# ProtoStack_Codec.net
KiCad netlist of a schematic drawn in Altium Designer
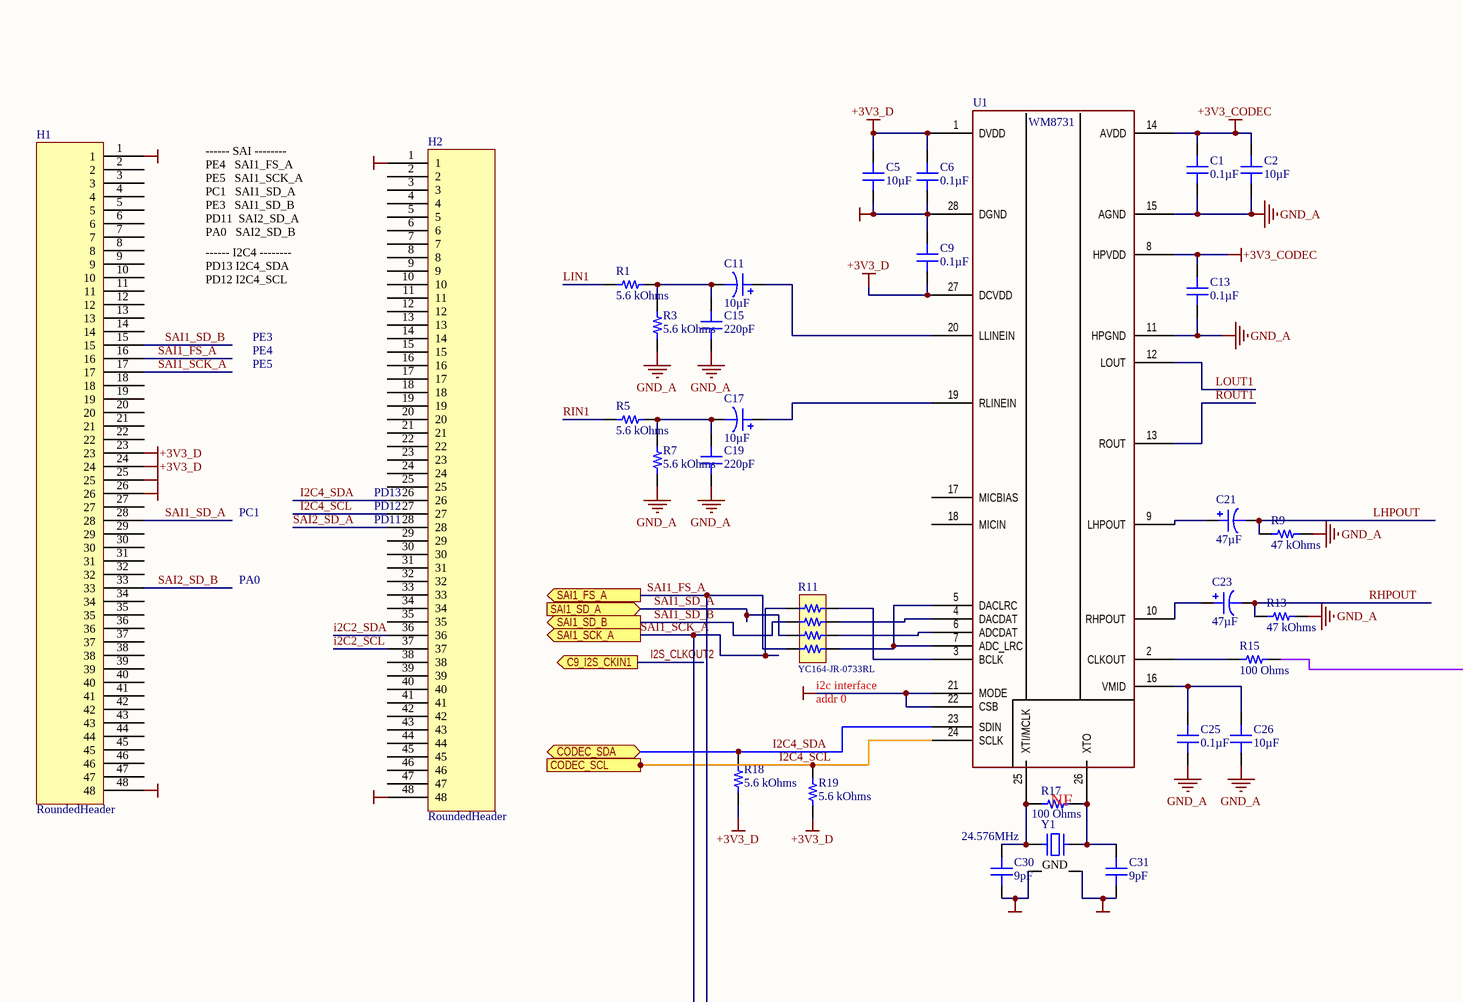
[diagram p0: ProtoStack_Codec.SchDoc, left]
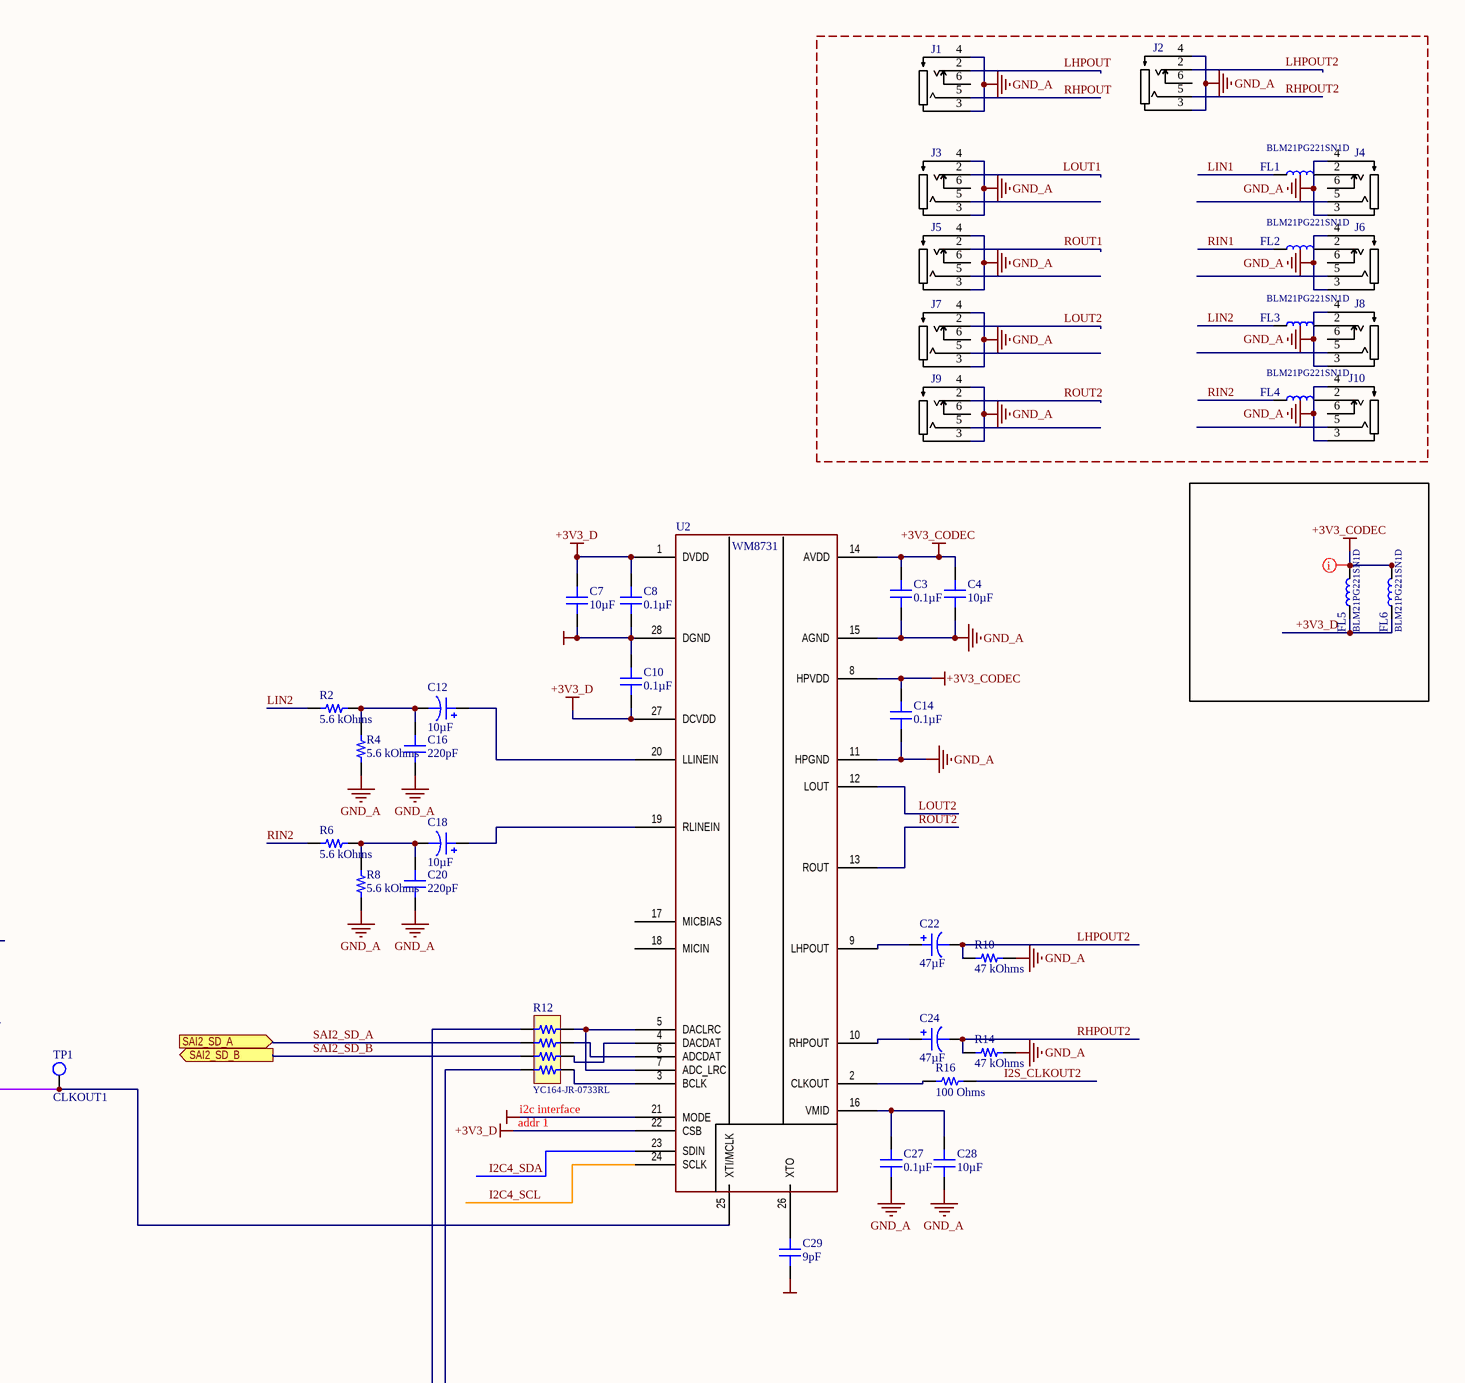
[diagram p1: ProtoStack_Codec.SchDoc, right]

(export (version "E")
  (design (tool "Eeschema 10.0.6"))
  (components
    (comp (ref "C1")
      (value "0.1µF")
      (footprint "CAP 0402_1005")
      (description "CAP CER 0.1UF 16V X7R 0402")
      (fields (field (name "PART NUMBER") "C0402C104K4RACAUTO") (field (name "MANUFACTURER") "KEMET"))
      (libsource (lib "Celestial Altium Library - altium_library") (part "Capacitor"))
    )
    (comp (ref "C2")
      (value "10µF")
      (footprint "CAP 0805_2012")
      (description "CAP CER 10UF 10V X5R 0805")
      (fields (field (name "PART NUMBER") "C0805C106K8PACTU") (field (name "MANUFACTURER") "KEMET"))
      (libsource (lib "Celestial Altium Library - altium_library") (part "Capacitor"))
    )
    (comp (ref "C3")
      (value "0.1µF")
      (footprint "CAP 0402_1005")
      (description "CAP CER 0.1UF 16V X7R 0402")
      (fields (field (name "PART NUMBER") "C0402C104K4RACAUTO") (field (name "MANUFACTURER") "KEMET"))
      (libsource (lib "Celestial Altium Library - altium_library") (part "Capacitor"))
    )
    (comp (ref "C4")
      (value "10µF")
      (footprint "CAP 0805_2012")
      (description "CAP CER 10UF 10V X5R 0805")
      (fields (field (name "PART NUMBER") "C0805C106K8PACTU") (field (name "MANUFACTURER") "KEMET"))
      (libsource (lib "Celestial Altium Library - altium_library") (part "Capacitor"))
    )
    (comp (ref "C5")
      (value "10µF")
      (footprint "CAP 0805_2012")
      (description "CAP CER 10UF 10V X5R 0805")
      (fields (field (name "PART NUMBER") "C0805C106K8PACTU") (field (name "MANUFACTURER") "KEMET"))
      (libsource (lib "Celestial Altium Library - altium_library") (part "Capacitor"))
    )
    (comp (ref "C6")
      (value "0.1µF")
      (footprint "CAP 0402_1005")
      (description "CAP CER 0.1UF 16V X7R 0402")
      (fields (field (name "PART NUMBER") "C0402C104K4RACAUTO") (field (name "MANUFACTURER") "KEMET"))
      (libsource (lib "Celestial Altium Library - altium_library") (part "Capacitor"))
    )
    (comp (ref "C7")
      (value "10µF")
      (footprint "CAP 0805_2012")
      (description "CAP CER 10UF 10V X5R 0805")
      (fields (field (name "PART NUMBER") "C0805C106K8PACTU") (field (name "MANUFACTURER") "KEMET"))
      (libsource (lib "Celestial Altium Library - altium_library") (part "Capacitor"))
    )
    (comp (ref "C8")
      (value "0.1µF")
      (footprint "CAP 0402_1005")
      (description "CAP CER 0.1UF 16V X7R 0402")
      (fields (field (name "PART NUMBER") "C0402C104K4RACAUTO") (field (name "MANUFACTURER") "KEMET"))
      (libsource (lib "Celestial Altium Library - altium_library") (part "Capacitor"))
    )
    (comp (ref "C9")
      (value "0.1µF")
      (footprint "CAP 0402_1005")
      (description "CAP CER 0.1UF 16V X7R 0402")
      (fields (field (name "PART NUMBER") "C0402C104K4RACAUTO") (field (name "MANUFACTURER") "KEMET"))
      (libsource (lib "Celestial Altium Library - altium_library") (part "Capacitor"))
    )
    (comp (ref "C10")
      (value "0.1µF")
      (footprint "CAP 0402_1005")
      (description "CAP CER 0.1UF 16V X7R 0402")
      (fields (field (name "PART NUMBER") "C0402C104K4RACAUTO") (field (name "MANUFACTURER") "KEMET"))
      (libsource (lib "Celestial Altium Library - altium_library") (part "Capacitor"))
    )
    (comp (ref "C11")
      (value "10µF")
      (footprint "CAP POL 1206_3216")
      (description "CAP TANT 10UF 10% 10V 1206")
      (fields (field (name "PART NUMBER") "T491A106K010AT") (field (name "MANUFACTURER") "KEMET"))
      (libsource (lib "Celestial Altium Library - altium_library") (part "Polarised Capacitor"))
    )
    (comp (ref "C12")
      (value "10µF")
      (footprint "CAP POL 1206_3216")
      (description "CAP TANT 10UF 10% 10V 1206")
      (fields (field (name "PART NUMBER") "T491A106K010AT") (field (name "MANUFACTURER") "KEMET"))
      (libsource (lib "Celestial Altium Library - altium_library") (part "Polarised Capacitor"))
    )
    (comp (ref "C13")
      (value "0.1µF")
      (footprint "CAP 0402_1005")
      (description "CAP CER 0.1UF 16V X7R 0402")
      (fields (field (name "PART NUMBER") "C0402C104K4RACAUTO") (field (name "MANUFACTURER") "KEMET"))
      (libsource (lib "Celestial Altium Library - altium_library") (part "Capacitor"))
    )
    (comp (ref "C14")
      (value "0.1µF")
      (footprint "CAP 0402_1005")
      (description "CAP CER 0.1UF 16V X7R 0402")
      (fields (field (name "PART NUMBER") "C0402C104K4RACAUTO") (field (name "MANUFACTURER") "KEMET"))
      (libsource (lib "Celestial Altium Library - altium_library") (part "Capacitor"))
    )
    (comp (ref "C15")
      (value "220pF")
      (footprint "CAP 0603_1608")
      (description "CAP CER 220PF 50V X7R 0603")
      (fields (field (name "PART NUMBER") "C0603C221K5RACTU") (field (name "MANUFACTURER") "KEMET"))
      (libsource (lib "Celestial Altium Library - altium_library") (part "Capacitor"))
    )
    (comp (ref "C16")
      (value "220pF")
      (footprint "CAP 0603_1608")
      (description "CAP CER 220PF 50V X7R 0603")
      (fields (field (name "PART NUMBER") "C0603C221K5RACTU") (field (name "MANUFACTURER") "KEMET"))
      (libsource (lib "Celestial Altium Library - altium_library") (part "Capacitor"))
    )
    (comp (ref "C17")
      (value "10µF")
      (footprint "CAP POL 1206_3216")
      (description "CAP TANT 10UF 10% 10V 1206")
      (fields (field (name "PART NUMBER") "T491A106K010AT") (field (name "MANUFACTURER") "KEMET"))
      (libsource (lib "Celestial Altium Library - altium_library") (part "Polarised Capacitor"))
    )
    (comp (ref "C18")
      (value "10µF")
      (footprint "CAP POL 1206_3216")
      (description "CAP TANT 10UF 10% 10V 1206")
      (fields (field (name "PART NUMBER") "T491A106K010AT") (field (name "MANUFACTURER") "KEMET"))
      (libsource (lib "Celestial Altium Library - altium_library") (part "Polarised Capacitor"))
    )
    (comp (ref "C19")
      (value "220pF")
      (footprint "CAP 0603_1608")
      (description "CAP CER 220PF 50V X7R 0603")
      (fields (field (name "PART NUMBER") "C0603C221K5RACTU") (field (name "MANUFACTURER") "KEMET"))
      (libsource (lib "Celestial Altium Library - altium_library") (part "Capacitor"))
    )
    (comp (ref "C20")
      (value "220pF")
      (footprint "CAP 0603_1608")
      (description "CAP CER 220PF 50V X7R 0603")
      (fields (field (name "PART NUMBER") "C0603C221K5RACTU") (field (name "MANUFACTURER") "KEMET"))
      (libsource (lib "Celestial Altium Library - altium_library") (part "Capacitor"))
    )
    (comp (ref "C21")
      (value "47µF")
      (footprint "CAP POL 2917_7343")
      (description "CAP TANT 47UF 10% 10V 2917")
      (fields (field (name "PART NUMBER") "293D476X9010D2TE3") (field (name "MANUFACTURER") "Vishay Sprague"))
      (libsource (lib "Celestial Altium Library - altium_library") (part "Polarised Capacitor"))
    )
    (comp (ref "C22")
      (value "47µF")
      (footprint "CAP POL 2917_7343")
      (description "CAP TANT 47UF 10% 10V 2917")
      (fields (field (name "PART NUMBER") "293D476X9010D2TE3") (field (name "MANUFACTURER") "Vishay Sprague"))
      (libsource (lib "Celestial Altium Library - altium_library") (part "Polarised Capacitor"))
    )
    (comp (ref "C23")
      (value "47µF")
      (footprint "CAP POL 2917_7343")
      (description "CAP TANT 47UF 10% 10V 2917")
      (fields (field (name "PART NUMBER") "293D476X9010D2TE3") (field (name "MANUFACTURER") "Vishay Sprague"))
      (libsource (lib "Celestial Altium Library - altium_library") (part "Polarised Capacitor"))
    )
    (comp (ref "C24")
      (value "47µF")
      (footprint "CAP POL 2917_7343")
      (description "CAP TANT 47UF 10% 10V 2917")
      (fields (field (name "PART NUMBER") "293D476X9010D2TE3") (field (name "MANUFACTURER") "Vishay Sprague"))
      (libsource (lib "Celestial Altium Library - altium_library") (part "Polarised Capacitor"))
    )
    (comp (ref "C25")
      (value "0.1µF")
      (footprint "CAP 0402_1005")
      (description "CAP CER 0.1UF 16V X7R 0402")
      (fields (field (name "PART NUMBER") "C0402C104K4RACAUTO") (field (name "MANUFACTURER") "KEMET"))
      (libsource (lib "Celestial Altium Library - altium_library") (part "Capacitor"))
    )
    (comp (ref "C26")
      (value "10µF")
      (footprint "CAP 0805_2012")
      (description "CAP CER 10UF 10V X5R 0805")
      (fields (field (name "PART NUMBER") "C0805C106K8PACTU") (field (name "MANUFACTURER") "KEMET"))
      (libsource (lib "Celestial Altium Library - altium_library") (part "Capacitor"))
    )
    (comp (ref "C27")
      (value "0.1µF")
      (footprint "CAP 0402_1005")
      (description "CAP CER 0.1UF 16V X7R 0402")
      (fields (field (name "PART NUMBER") "C0402C104K4RACAUTO") (field (name "MANUFACTURER") "KEMET"))
      (libsource (lib "Celestial Altium Library - altium_library") (part "Capacitor"))
    )
    (comp (ref "C28")
      (value "10µF")
      (footprint "CAP 0805_2012")
      (description "CAP CER 10UF 10V X5R 0805")
      (fields (field (name "PART NUMBER") "C0805C106K8PACTU") (field (name "MANUFACTURER") "KEMET"))
      (libsource (lib "Celestial Altium Library - altium_library") (part "Capacitor"))
    )
    (comp (ref "C29")
      (value "9pF")
      (footprint "CAP 0805_2012")
      (description "CAP CER 9PF 250V C0G/NP0 0805")
      (fields (field (name "PART NUMBER") "CBR08C909CAGAC") (field (name "MANUFACTURER") "KEMET"))
      (libsource (lib "Celestial Altium Library - altium_library") (part "Capacitor"))
    )
    (comp (ref "C30")
      (value "9pF")
      (footprint "CAP 0805_2012")
      (description "CAP CER 9PF 250V C0G/NP0 0805")
      (fields (field (name "PART NUMBER") "CBR08C909CAGAC") (field (name "MANUFACTURER") "KEMET"))
      (libsource (lib "Celestial Altium Library - altium_library") (part "Capacitor"))
    )
    (comp (ref "C31")
      (value "9pF")
      (footprint "CAP 0805_2012")
      (description "CAP CER 9PF 250V C0G/NP0 0805")
      (fields (field (name "PART NUMBER") "CBR08C909CAGAC") (field (name "MANUFACTURER") "KEMET"))
      (libsource (lib "Celestial Altium Library - altium_library") (part "Capacitor"))
    )
    (comp (ref "FL1")
      (value "BLM21PG221SN1D")
      (footprint "0805_IND")
      (description "ACM Series 0805 360 Ohm 220mA 500 mOhm DCR 50 V SMT Common Mode Filter")
      (libsource (lib "ProtoStack_H750VBT") (part "BLM21PG221SN1D"))
    )
    (comp (ref "FL2")
      (value "BLM21PG221SN1D")
      (footprint "0805_IND")
      (description "ACM Series 0805 360 Ohm 220mA 500 mOhm DCR 50 V SMT Common Mode Filter")
      (libsource (lib "ProtoStack_H750VBT") (part "BLM21PG221SN1D"))
    )
    (comp (ref "FL3")
      (value "BLM21PG221SN1D")
      (footprint "0805_IND")
      (description "ACM Series 0805 360 Ohm 220mA 500 mOhm DCR 50 V SMT Common Mode Filter")
      (libsource (lib "ProtoStack_H750VBT") (part "BLM21PG221SN1D"))
    )
    (comp (ref "FL4")
      (value "BLM21PG221SN1D")
      (footprint "0805_IND")
      (description "ACM Series 0805 360 Ohm 220mA 500 mOhm DCR 50 V SMT Common Mode Filter")
      (libsource (lib "ProtoStack_H750VBT") (part "BLM21PG221SN1D"))
    )
    (comp (ref "FL5")
      (value "BLM21PG221SN1D")
      (footprint "0805_IND")
      (description "ACM Series 0805 360 Ohm 220mA 500 mOhm DCR 50 V SMT Common Mode Filter")
      (libsource (lib "") (part "BLM21PG221SN1D_1"))
    )
    (comp (ref "FL6")
      (value "BLM21PG221SN1D")
      (footprint "0805_IND")
      (description "ACM Series 0805 360 Ohm 220mA 500 mOhm DCR 50 V SMT Common Mode Filter")
      (libsource (lib "") (part "BLM21PG221SN1D_1"))
    )
    (comp (ref "H1")
      (value "RoundedHeader")
      (footprint "ProtoStack_H750VBT:HeaderDtack_48")
      (libsource (lib "") (part "HeaderStack_48_1"))
    )
    (comp (ref "H2")
      (value "RoundedHeader")
      (footprint "ProtoStack_H750VBT:HeaderDtack_48")
      (libsource (lib "ProtoStack_H750VBT") (part "HeaderStack_48"))
    )
    (comp (ref "J1")
      (value "~")
      (footprint "PJ_327")
      (description "Conn 3.5MM Stereo Jack F 3 POS Solder RA SMD 3 Terminal 1 Port T/R")
      (fields (field (name "MP") "35RASMT2BHNTRX") (field (name "MF") "Switchcraft"))
      (libsource (lib "ProtoStack_H750VBT") (part "3.5mm jack stereo smd"))
    )
    (comp (ref "J2")
      (value "~")
      (footprint "PJ_327")
      (description "Conn 3.5MM Stereo Jack F 3 POS Solder RA SMD 3 Terminal 1 Port T/R")
      (fields (field (name "MP") "35RASMT2BHNTRX") (field (name "MF") "Switchcraft"))
      (libsource (lib "ProtoStack_H750VBT") (part "3.5mm jack stereo smd"))
    )
    (comp (ref "J3")
      (value "~")
      (footprint "PJ_327")
      (description "Conn 3.5MM Stereo Jack F 3 POS Solder RA SMD 3 Terminal 1 Port T/R")
      (fields (field (name "MP") "35RASMT2BHNTRX") (field (name "MF") "Switchcraft"))
      (libsource (lib "ProtoStack_H750VBT") (part "3.5mm jack stereo smd"))
    )
    (comp (ref "J4")
      (value "~")
      (footprint "PJ_327")
      (description "Conn 3.5MM Stereo Jack F 3 POS Solder RA SMD 3 Terminal 1 Port T/R")
      (fields (field (name "MP") "35RASMT2BHNTRX") (field (name "MF") "Switchcraft"))
      (libsource (lib "ProtoStack_H750VBT") (part "3.5mm jack stereo smd"))
    )
    (comp (ref "J5")
      (value "~")
      (footprint "PJ_327")
      (description "Conn 3.5MM Stereo Jack F 3 POS Solder RA SMD 3 Terminal 1 Port T/R")
      (fields (field (name "MP") "35RASMT2BHNTRX") (field (name "MF") "Switchcraft"))
      (libsource (lib "ProtoStack_H750VBT") (part "3.5mm jack stereo smd"))
    )
    (comp (ref "J6")
      (value "~")
      (footprint "PJ_327")
      (description "Conn 3.5MM Stereo Jack F 3 POS Solder RA SMD 3 Terminal 1 Port T/R")
      (fields (field (name "MP") "35RASMT2BHNTRX") (field (name "MF") "Switchcraft"))
      (libsource (lib "ProtoStack_H750VBT") (part "3.5mm jack stereo smd"))
    )
    (comp (ref "J7")
      (value "~")
      (footprint "PJ_327")
      (description "Conn 3.5MM Stereo Jack F 3 POS Solder RA SMD 3 Terminal 1 Port T/R")
      (fields (field (name "MP") "35RASMT2BHNTRX") (field (name "MF") "Switchcraft"))
      (libsource (lib "ProtoStack_H750VBT") (part "3.5mm jack stereo smd"))
    )
    (comp (ref "J8")
      (value "~")
      (footprint "PJ_327")
      (description "Conn 3.5MM Stereo Jack F 3 POS Solder RA SMD 3 Terminal 1 Port T/R")
      (fields (field (name "MP") "35RASMT2BHNTRX") (field (name "MF") "Switchcraft"))
      (libsource (lib "ProtoStack_H750VBT") (part "3.5mm jack stereo smd"))
    )
    (comp (ref "J9")
      (value "~")
      (footprint "PJ_327")
      (description "Conn 3.5MM Stereo Jack F 3 POS Solder RA SMD 3 Terminal 1 Port T/R")
      (fields (field (name "MP") "35RASMT2BHNTRX") (field (name "MF") "Switchcraft"))
      (libsource (lib "ProtoStack_H750VBT") (part "3.5mm jack stereo smd"))
    )
    (comp (ref "J10")
      (value "~")
      (footprint "PJ_327")
      (description "Conn 3.5MM Stereo Jack F 3 POS Solder RA SMD 3 Terminal 1 Port T/R")
      (fields (field (name "MP") "35RASMT2BHNTRX") (field (name "MF") "Switchcraft"))
      (libsource (lib "ProtoStack_H750VBT") (part "3.5mm jack stereo smd"))
    )
    (comp (ref "R1")
      (value "5.6 kOhms")
      (footprint "RES 0603_1608")
      (description "RES SMD 5.6K OHM 0.5% 1/10W 0603")
      (fields (field (name "PART NUMBER") "RT0603DRE075K6L") (field (name "MANUFACTURER") "Yageo"))
      (libsource (lib "Celestial Altium Library - altium_library") (part "Resistor"))
    )
    (comp (ref "R2")
      (value "5.6 kOhms")
      (footprint "RES 0603_1608")
      (description "RES SMD 5.6K OHM 0.5% 1/10W 0603")
      (fields (field (name "PART NUMBER") "RT0603DRE075K6L") (field (name "MANUFACTURER") "Yageo"))
      (libsource (lib "Celestial Altium Library - altium_library") (part "Resistor"))
    )
    (comp (ref "R3")
      (value "5.6 kOhms")
      (footprint "RES 0603_1608")
      (description "RES SMD 5.6K OHM 0.5% 1/10W 0603")
      (fields (field (name "PART NUMBER") "RT0603DRE075K6L") (field (name "MANUFACTURER") "Yageo"))
      (libsource (lib "Celestial Altium Library - altium_library") (part "Resistor"))
    )
    (comp (ref "R4")
      (value "5.6 kOhms")
      (footprint "RES 0603_1608")
      (description "RES SMD 5.6K OHM 0.5% 1/10W 0603")
      (fields (field (name "PART NUMBER") "RT0603DRE075K6L") (field (name "MANUFACTURER") "Yageo"))
      (libsource (lib "Celestial Altium Library - altium_library") (part "Resistor"))
    )
    (comp (ref "R5")
      (value "5.6 kOhms")
      (footprint "RES 0603_1608")
      (description "RES SMD 5.6K OHM 0.5% 1/10W 0603")
      (fields (field (name "PART NUMBER") "RT0603DRE075K6L") (field (name "MANUFACTURER") "Yageo"))
      (libsource (lib "Celestial Altium Library - altium_library") (part "Resistor"))
    )
    (comp (ref "R6")
      (value "5.6 kOhms")
      (footprint "RES 0603_1608")
      (description "RES SMD 5.6K OHM 0.5% 1/10W 0603")
      (fields (field (name "PART NUMBER") "RT0603DRE075K6L") (field (name "MANUFACTURER") "Yageo"))
      (libsource (lib "Celestial Altium Library - altium_library") (part "Resistor"))
    )
    (comp (ref "R7")
      (value "5.6 kOhms")
      (footprint "RES 0603_1608")
      (description "RES SMD 5.6K OHM 0.5% 1/10W 0603")
      (fields (field (name "PART NUMBER") "RT0603DRE075K6L") (field (name "MANUFACTURER") "Yageo"))
      (libsource (lib "Celestial Altium Library - altium_library") (part "Resistor"))
    )
    (comp (ref "R8")
      (value "5.6 kOhms")
      (footprint "RES 0603_1608")
      (description "RES SMD 5.6K OHM 0.5% 1/10W 0603")
      (fields (field (name "PART NUMBER") "RT0603DRE075K6L") (field (name "MANUFACTURER") "Yageo"))
      (libsource (lib "Celestial Altium Library - altium_library") (part "Resistor"))
    )
    (comp (ref "R9")
      (value "47 kOhms")
      (footprint "RES 0603_1608")
      (description "RES SMD 47K OHM 1% 1/10W 0603")
      (fields (field (name "PART NUMBER") "RT0603FRE0747KL") (field (name "MANUFACTURER") "Yageo"))
      (libsource (lib "Celestial Altium Library - altium_library") (part "Resistor"))
    )
    (comp (ref "R10")
      (value "47 kOhms")
      (footprint "RES 0603_1608")
      (description "RES SMD 47K OHM 1% 1/10W 0603")
      (fields (field (name "PART NUMBER") "RT0603FRE0747KL") (field (name "MANUFACTURER") "Yageo"))
      (libsource (lib "Celestial Altium Library - altium_library") (part "Resistor"))
    )
    (comp (ref "R11")
      (value "YC164-JR-0733RL")
      (footprint "RESNET 1206-8 CONVEX")
      (description "RES ARRAY 4 RES 33 OHM 1206")
      (fields (field (name "MANUFACTURER") "Yageo") (field (name "TOLERANCE") "±5%"))
      (libsource (lib "Celestial Altium Library - altium_library") (part "Resistor Array (4 circuit)"))
    )
    (comp (ref "R12")
      (value "YC164-JR-0733RL")
      (footprint "RESNET 1206-8 CONVEX")
      (description "RES ARRAY 4 RES 33 OHM 1206")
      (fields (field (name "MANUFACTURER") "Yageo") (field (name "TOLERANCE") "±5%"))
      (libsource (lib "Celestial Altium Library - altium_library") (part "Resistor Array (4 circuit)"))
    )
    (comp (ref "R13")
      (value "47 kOhms")
      (footprint "RES 0603_1608")
      (description "RES SMD 47K OHM 1% 1/10W 0603")
      (fields (field (name "PART NUMBER") "RT0603FRE0747KL") (field (name "MANUFACTURER") "Yageo"))
      (libsource (lib "Celestial Altium Library - altium_library") (part "Resistor"))
    )
    (comp (ref "R14")
      (value "47 kOhms")
      (footprint "RES 0603_1608")
      (description "RES SMD 47K OHM 1% 1/10W 0603")
      (fields (field (name "PART NUMBER") "RT0603FRE0747KL") (field (name "MANUFACTURER") "Yageo"))
      (libsource (lib "Celestial Altium Library - altium_library") (part "Resistor"))
    )
    (comp (ref "R15")
      (value "100 Ohms")
      (footprint "RES 0402_1005")
      (description "RES SMD 100 OHM 1% 1/16W 0402")
      (fields (field (name "PART NUMBER") "RT0402FRE07100RL") (field (name "MANUFACTURER") "Yageo"))
      (libsource (lib "Celestial Altium Library - altium_library") (part "Resistor"))
    )
    (comp (ref "R16")
      (value "100 Ohms")
      (footprint "RES 0402_1005")
      (description "RES SMD 100 OHM 1% 1/16W 0402")
      (fields (field (name "PART NUMBER") "RT0402FRE07100RL") (field (name "MANUFACTURER") "Yageo"))
      (libsource (lib "Celestial Altium Library - altium_library") (part "Resistor"))
    )
    (comp (ref "R17")
      (value "100 Ohms")
      (footprint "RES 0402_1005")
      (description "RES SMD 100 OHM 1% 1/16W 0402")
      (fields (field (name "PART NUMBER") "RT0402FRE07100RL") (field (name "MANUFACTURER") "Yageo"))
      (libsource (lib "Celestial Altium Library - altium_library") (part "Resistor"))
    )
    (comp (ref "R18")
      (value "5.6 kOhms")
      (footprint "RES 0603_1608")
      (description "RES SMD 5.6K OHM 0.5% 1/10W 0603")
      (fields (field (name "PART NUMBER") "RT0603DRE075K6L") (field (name "MANUFACTURER") "Yageo"))
      (libsource (lib "Celestial Altium Library - altium_library") (part "Resistor"))
    )
    (comp (ref "R19")
      (value "5.6 kOhms")
      (footprint "RES 0603_1608")
      (description "RES SMD 5.6K OHM 0.5% 1/10W 0603")
      (fields (field (name "PART NUMBER") "RT0603DRE075K6L") (field (name "MANUFACTURER") "Yageo"))
      (libsource (lib "Celestial Altium Library - altium_library") (part "Resistor"))
    )
    (comp (ref "TP1")
      (value "CLKOUT1")
      (footprint "TESTPOINT")
      (libsource (lib "DAC_ADC") (part "TestPoint"))
    )
    (comp (ref "U1")
      (value "WM8731")
      (footprint "TSSOP-28")
      (description "Stero in/ot audio codec")
      (libsource (lib "DAC_ADC") (part "WM8731"))
    )
    (comp (ref "U2")
      (value "WM8731")
      (footprint "TSSOP-28")
      (description "Stero in/ot audio codec")
      (libsource (lib "DAC_ADC") (part "WM8731"))
    )
    (comp (ref "Y1")
      (value "24.576MHz")
      (footprint "ABRACON ABM8G")
      (description "CRYSTAL 24.5760MHZ 10PF SMD")
      (fields
        (field (name "PART NUMBER") "ABM8G-24.576MHZ-B4Y-T")
        (field (name "MANUFACTURER") "Abracon LLC")
      )
      (libsource (lib "Celestial Altium Library - altium_library") (part "Abracon Crystal ABM8G"))
    )
  )
  (nets
    (net (code "1") (name "+3V3_CODEC") (class "Default")
      (node (ref "C1") (pin "2") (pinfunction "2_2") (pintype "passive"))
      (node (ref "C13") (pin "2") (pinfunction "2_2") (pintype "passive"))
      (node (ref "C14") (pin "2") (pinfunction "2_2") (pintype "passive"))
      (node (ref "C2") (pin "2") (pinfunction "2_2") (pintype "passive"))
      (node (ref "C3") (pin "2") (pinfunction "2_2") (pintype "passive"))
      (node (ref "C4") (pin "2") (pinfunction "2_2") (pintype "passive"))
      (node (ref "FL5") (pin "2") (pinfunction "2_2") (pintype "passive"))
      (node (ref "FL6") (pin "2") (pinfunction "2_2") (pintype "passive"))
      (node (ref "U1") (pin "14") (pinfunction "AVDD_14") (pintype "passive"))
      (node (ref "U1") (pin "8") (pinfunction "HPVDD_8") (pintype "passive"))
      (node (ref "U2") (pin "14") (pinfunction "AVDD_14") (pintype "passive"))
      (node (ref "U2") (pin "8") (pinfunction "HPVDD_8") (pintype "passive"))
    )
    (net (code "2") (name "+3V3_D") (class "Default")
      (node (ref "C10") (pin "1") (pinfunction "1_1") (pintype "passive"))
      (node (ref "C5") (pin "2") (pinfunction "2_2") (pintype "passive"))
      (node (ref "C6") (pin "2") (pinfunction "2_2") (pintype "passive"))
      (node (ref "C7") (pin "2") (pinfunction "2_2") (pintype "passive"))
      (node (ref "C8") (pin "2") (pinfunction "2_2") (pintype "passive"))
      (node (ref "C9") (pin "1") (pinfunction "1_1") (pintype "passive"))
      (node (ref "FL5") (pin "1") (pinfunction "1_1") (pintype "passive"))
      (node (ref "FL6") (pin "1") (pinfunction "1_1") (pintype "passive"))
      (node (ref "H1") (pin "23") (pinfunction "23_23") (pintype "passive"))
      (node (ref "H1") (pin "24") (pinfunction "24_24") (pintype "passive"))
      (node (ref "R18") (pin "1") (pinfunction "1_1") (pintype "passive"))
      (node (ref "R19") (pin "1") (pinfunction "1_1") (pintype "passive"))
      (node (ref "U1") (pin "1") (pinfunction "DVDD_1") (pintype "passive"))
      (node (ref "U1") (pin "27") (pinfunction "DCVDD_27") (pintype "passive"))
      (node (ref "U2") (pin "1") (pinfunction "DVDD_1") (pintype "passive"))
      (node (ref "U2") (pin "22") (pinfunction "CSB_22") (pintype "passive"))
      (node (ref "U2") (pin "27") (pinfunction "DCVDD_27") (pintype "passive"))
    )
    (net (code "3") (name "/I2C4_SCL") (class "Default")
      (node (ref "H2") (pin "27") (pinfunction "27_27") (pintype "passive"))
      (node (ref "R19") (pin "2") (pinfunction "2_2") (pintype "passive"))
      (node (ref "U1") (pin "24") (pinfunction "SCLK_24") (pintype "passive"))
      (node (ref "U2") (pin "24") (pinfunction "SCLK_24") (pintype "passive"))
    )
    (net (code "4") (name "/I2C4_SDA") (class "Default")
      (node (ref "H2") (pin "26") (pinfunction "26_26") (pintype "passive"))
      (node (ref "R18") (pin "2") (pinfunction "2_2") (pintype "passive"))
      (node (ref "U1") (pin "23") (pinfunction "SDIN_23") (pintype "passive"))
      (node (ref "U2") (pin "23") (pinfunction "SDIN_23") (pintype "passive"))
    )
    (net (code "5") (name "/I2S_CLKOUT2") (class "Default")
      (node (ref "R16") (pin "2") (pinfunction "2_2") (pintype "passive"))
    )
    (net (code "6") (name "/LHPOUT") (class "Default")
      (node (ref "C21") (pin "2") (pinfunction "2_2") (pintype "passive"))
      (node (ref "J1") (pin "2") (pinfunction "2_2") (pintype "passive"))
      (node (ref "R9") (pin "1") (pinfunction "1_1") (pintype "passive"))
    )
    (net (code "7") (name "/LHPOUT2") (class "Default")
      (node (ref "C22") (pin "2") (pinfunction "2_2") (pintype "passive"))
      (node (ref "J2") (pin "2") (pinfunction "2_2") (pintype "passive"))
      (node (ref "R10") (pin "1") (pinfunction "1_1") (pintype "passive"))
    )
    (net (code "8") (name "/LIN1") (class "Default")
      (node (ref "FL1") (pin "1") (pinfunction "1_1") (pintype "passive"))
      (node (ref "R1") (pin "1") (pinfunction "1_1") (pintype "passive"))
    )
    (net (code "9") (name "/LIN2") (class "Default")
      (node (ref "FL3") (pin "1") (pinfunction "1_1") (pintype "passive"))
      (node (ref "R2") (pin "1") (pinfunction "1_1") (pintype "passive"))
    )
    (net (code "10") (name "/LOUT1") (class "Default")
      (node (ref "J3") (pin "2") (pinfunction "2_2") (pintype "passive"))
      (node (ref "U1") (pin "12") (pinfunction "LOUT_12") (pintype "passive"))
    )
    (net (code "11") (name "/LOUT2") (class "Default")
      (node (ref "J7") (pin "2") (pinfunction "2_2") (pintype "passive"))
      (node (ref "U2") (pin "12") (pinfunction "LOUT_12") (pintype "passive"))
    )
    (net (code "12") (name "/RHPOUT") (class "Default")
      (node (ref "C23") (pin "2") (pinfunction "2_2") (pintype "passive"))
      (node (ref "J1") (pin "5") (pinfunction "3_5") (pintype "passive"))
      (node (ref "R13") (pin "1") (pinfunction "1_1") (pintype "passive"))
    )
    (net (code "13") (name "/RHPOUT2") (class "Default")
      (node (ref "C24") (pin "2") (pinfunction "2_2") (pintype "passive"))
      (node (ref "J2") (pin "5") (pinfunction "3_5") (pintype "passive"))
      (node (ref "R14") (pin "1") (pinfunction "1_1") (pintype "passive"))
    )
    (net (code "14") (name "/RIN1") (class "Default")
      (node (ref "FL2") (pin "1") (pinfunction "1_1") (pintype "passive"))
      (node (ref "R5") (pin "1") (pinfunction "1_1") (pintype "passive"))
    )
    (net (code "15") (name "/RIN2") (class "Default")
      (node (ref "FL4") (pin "1") (pinfunction "1_1") (pintype "passive"))
      (node (ref "R6") (pin "1") (pinfunction "1_1") (pintype "passive"))
    )
    (net (code "16") (name "/ROUT1") (class "Default")
      (node (ref "J5") (pin "2") (pinfunction "2_2") (pintype "passive"))
      (node (ref "U1") (pin "13") (pinfunction "ROUT_13") (pintype "passive"))
    )
    (net (code "17") (name "/ROUT2") (class "Default")
      (node (ref "J9") (pin "2") (pinfunction "2_2") (pintype "passive"))
      (node (ref "U2") (pin "13") (pinfunction "ROUT_13") (pintype "passive"))
    )
    (net (code "18") (name "/SAI1_FS_A") (class "Default")
      (node (ref "H1") (pin "16") (pinfunction "16_16") (pintype "passive"))
      (node (ref "R11") (pin "4") (pinfunction "4_4") (pintype "passive"))
      (node (ref "R12") (pin "1") (pinfunction "1_1") (pintype "passive"))
    )
    (net (code "19") (name "/SAI1_SCK_A") (class "Default")
      (node (ref "H1") (pin "17") (pinfunction "17_17") (pintype "passive"))
      (node (ref "R11") (pin "1") (pinfunction "1_1") (pintype "passive"))
      (node (ref "R12") (pin "4") (pinfunction "4_4") (pintype "passive"))
    )
    (net (code "20") (name "/SAI1_SD_A") (class "Default")
      (node (ref "H1") (pin "28") (pinfunction "28_28") (pintype "passive"))
      (node (ref "R11") (pin "3") (pinfunction "3_3") (pintype "passive"))
    )
    (net (code "21") (name "/SAI1_SD_B") (class "Default")
      (node (ref "H1") (pin "15") (pinfunction "15_15") (pintype "passive"))
      (node (ref "R11") (pin "2") (pinfunction "2_2") (pintype "passive"))
    )
    (net (code "22") (name "/SAI2_SD_A") (class "Default")
      (node (ref "H2") (pin "28") (pinfunction "28_28") (pintype "passive"))
      (node (ref "R12") (pin "2") (pinfunction "2_2") (pintype "passive"))
    )
    (net (code "23") (name "/SAI2_SD_B") (class "Default")
      (node (ref "H1") (pin "33") (pinfunction "33_33") (pintype "passive"))
      (node (ref "R12") (pin "3") (pinfunction "3_3") (pintype "passive"))
    )
    (net (code "24") (name "/i2C2_SCL") (class "Default")
      (node (ref "H2") (pin "37") (pinfunction "37_37") (pintype "passive"))
    )
    (net (code "25") (name "/i2C2_SDA") (class "Default")
      (node (ref "H2") (pin "36") (pinfunction "36_36") (pintype "passive"))
    )
    (net (code "26") (name "GND") (class "Default")
      (node (ref "C10") (pin "2") (pinfunction "2_2") (pintype "passive"))
      (node (ref "C29") (pin "2") (pinfunction "2_2") (pintype "passive"))
      (node (ref "C30") (pin "2") (pinfunction "2_2") (pintype "passive"))
      (node (ref "C31") (pin "2") (pinfunction "2_2") (pintype "passive"))
      (node (ref "C5") (pin "1") (pinfunction "1_1") (pintype "passive"))
      (node (ref "C6") (pin "1") (pinfunction "1_1") (pintype "passive"))
      (node (ref "C7") (pin "1") (pinfunction "1_1") (pintype "passive"))
      (node (ref "C8") (pin "1") (pinfunction "1_1") (pintype "passive"))
      (node (ref "C9") (pin "2") (pinfunction "2_2") (pintype "passive"))
      (node (ref "H1") (pin "1") (pinfunction "1_1") (pintype "passive"))
      (node (ref "H1") (pin "25") (pinfunction "25_25") (pintype "passive"))
      (node (ref "H1") (pin "26") (pinfunction "26_26") (pintype "passive"))
      (node (ref "H1") (pin "48") (pinfunction "48_48") (pintype "passive"))
      (node (ref "H2") (pin "1") (pinfunction "1_1") (pintype "passive"))
      (node (ref "H2") (pin "48") (pinfunction "48_48") (pintype "passive"))
      (node (ref "U1") (pin "21") (pinfunction "MODE_21") (pintype "passive"))
      (node (ref "U1") (pin "22") (pinfunction "CSB_22") (pintype "passive"))
      (node (ref "U1") (pin "28") (pinfunction "DGND_28") (pintype "passive"))
      (node (ref "U2") (pin "21") (pinfunction "MODE_21") (pintype "passive"))
      (node (ref "U2") (pin "28") (pinfunction "DGND_28") (pintype "passive"))
      (node (ref "Y1") (pin "2") (pinfunction "GND_2") (pintype "passive"))
      (node (ref "Y1") (pin "4") (pinfunction "GND_4") (pintype "passive"))
    )
    (net (code "27") (name "GND_A") (class "Default")
      (node (ref "C1") (pin "1") (pinfunction "1_1") (pintype "passive"))
      (node (ref "C13") (pin "1") (pinfunction "1_1") (pintype "passive"))
      (node (ref "C14") (pin "1") (pinfunction "1_1") (pintype "passive"))
      (node (ref "C15") (pin "1") (pinfunction "1_1") (pintype "passive"))
      (node (ref "C16") (pin "1") (pinfunction "1_1") (pintype "passive"))
      (node (ref "C19") (pin "1") (pinfunction "1_1") (pintype "passive"))
      (node (ref "C2") (pin "1") (pinfunction "1_1") (pintype "passive"))
      (node (ref "C20") (pin "1") (pinfunction "1_1") (pintype "passive"))
      (node (ref "C25") (pin "2") (pinfunction "2_2") (pintype "passive"))
      (node (ref "C26") (pin "2") (pinfunction "2_2") (pintype "passive"))
      (node (ref "C27") (pin "2") (pinfunction "2_2") (pintype "passive"))
      (node (ref "C28") (pin "2") (pinfunction "2_2") (pintype "passive"))
      (node (ref "C3") (pin "1") (pinfunction "1_1") (pintype "passive"))
      (node (ref "C4") (pin "1") (pinfunction "1_1") (pintype "passive"))
      (node (ref "J1") (pin "3") (pinfunction "1_3") (pintype "passive"))
      (node (ref "J1") (pin "4") (pinfunction "5_4") (pintype "passive"))
      (node (ref "J10") (pin "3") (pinfunction "1_3") (pintype "passive"))
      (node (ref "J10") (pin "4") (pinfunction "5_4") (pintype "passive"))
      (node (ref "J2") (pin "3") (pinfunction "1_3") (pintype "passive"))
      (node (ref "J2") (pin "4") (pinfunction "5_4") (pintype "passive"))
      (node (ref "J3") (pin "3") (pinfunction "1_3") (pintype "passive"))
      (node (ref "J3") (pin "4") (pinfunction "5_4") (pintype "passive"))
      (node (ref "J4") (pin "3") (pinfunction "1_3") (pintype "passive"))
      (node (ref "J4") (pin "4") (pinfunction "5_4") (pintype "passive"))
      (node (ref "J5") (pin "3") (pinfunction "1_3") (pintype "passive"))
      (node (ref "J5") (pin "4") (pinfunction "5_4") (pintype "passive"))
      (node (ref "J6") (pin "3") (pinfunction "1_3") (pintype "passive"))
      (node (ref "J6") (pin "4") (pinfunction "5_4") (pintype "passive"))
      (node (ref "J7") (pin "3") (pinfunction "1_3") (pintype "passive"))
      (node (ref "J7") (pin "4") (pinfunction "5_4") (pintype "passive"))
      (node (ref "J8") (pin "3") (pinfunction "1_3") (pintype "passive"))
      (node (ref "J8") (pin "4") (pinfunction "5_4") (pintype "passive"))
      (node (ref "J9") (pin "3") (pinfunction "1_3") (pintype "passive"))
      (node (ref "J9") (pin "4") (pinfunction "5_4") (pintype "passive"))
      (node (ref "R10") (pin "2") (pinfunction "2_2") (pintype "passive"))
      (node (ref "R13") (pin "2") (pinfunction "2_2") (pintype "passive"))
      (node (ref "R14") (pin "2") (pinfunction "2_2") (pintype "passive"))
      (node (ref "R3") (pin "1") (pinfunction "1_1") (pintype "passive"))
      (node (ref "R4") (pin "1") (pinfunction "1_1") (pintype "passive"))
      (node (ref "R7") (pin "1") (pinfunction "1_1") (pintype "passive"))
      (node (ref "R8") (pin "1") (pinfunction "1_1") (pintype "passive"))
      (node (ref "R9") (pin "2") (pinfunction "2_2") (pintype "passive"))
      (node (ref "U1") (pin "11") (pinfunction "HPGND_11") (pintype "passive"))
      (node (ref "U1") (pin "15") (pinfunction "AGND_15") (pintype "passive"))
      (node (ref "U2") (pin "11") (pinfunction "HPGND_11") (pintype "passive"))
      (node (ref "U2") (pin "15") (pinfunction "AGND_15") (pintype "passive"))
    )
    (net (code "28") (name "Net-(C11-Pad2)") (class "Default")
      (node (ref "C11") (pin "2") (pinfunction "2_2") (pintype "passive"))
      (node (ref "C15") (pin "2") (pinfunction "2_2") (pintype "passive"))
      (node (ref "R1") (pin "2") (pinfunction "2_2") (pintype "passive"))
      (node (ref "R3") (pin "2") (pinfunction "2_2") (pintype "passive"))
    )
    (net (code "29") (name "Net-(C12-Pad2)") (class "Default")
      (node (ref "C12") (pin "2") (pinfunction "2_2") (pintype "passive"))
      (node (ref "C16") (pin "2") (pinfunction "2_2") (pintype "passive"))
      (node (ref "R2") (pin "2") (pinfunction "2_2") (pintype "passive"))
      (node (ref "R4") (pin "2") (pinfunction "2_2") (pintype "passive"))
    )
    (net (code "30") (name "Net-(C17-Pad2)") (class "Default")
      (node (ref "C17") (pin "2") (pinfunction "2_2") (pintype "passive"))
      (node (ref "C19") (pin "2") (pinfunction "2_2") (pintype "passive"))
      (node (ref "R5") (pin "2") (pinfunction "2_2") (pintype "passive"))
      (node (ref "R7") (pin "2") (pinfunction "2_2") (pintype "passive"))
    )
    (net (code "31") (name "Net-(C18-Pad2)") (class "Default")
      (node (ref "C18") (pin "2") (pinfunction "2_2") (pintype "passive"))
      (node (ref "C20") (pin "2") (pinfunction "2_2") (pintype "passive"))
      (node (ref "R6") (pin "2") (pinfunction "2_2") (pintype "passive"))
      (node (ref "R8") (pin "2") (pinfunction "2_2") (pintype "passive"))
    )
    (net (code "32") (name "Net-(FL1-Pad2)") (class "Default")
      (node (ref "FL1") (pin "2") (pinfunction "2_2") (pintype "passive"))
      (node (ref "J4") (pin "2") (pinfunction "2_2") (pintype "passive"))
    )
    (net (code "33") (name "Net-(FL2-Pad2)") (class "Default")
      (node (ref "FL2") (pin "2") (pinfunction "2_2") (pintype "passive"))
      (node (ref "J6") (pin "2") (pinfunction "2_2") (pintype "passive"))
    )
    (net (code "34") (name "Net-(FL3-Pad2)") (class "Default")
      (node (ref "FL3") (pin "2") (pinfunction "2_2") (pintype "passive"))
      (node (ref "J8") (pin "2") (pinfunction "2_2") (pintype "passive"))
    )
    (net (code "35") (name "Net-(FL4-Pad2)") (class "Default")
      (node (ref "FL4") (pin "2") (pinfunction "2_2") (pintype "passive"))
      (node (ref "J10") (pin "2") (pinfunction "2_2") (pintype "passive"))
    )
    (net (code "36") (name "Net-(TP1-12)") (class "Default")
      (node (ref "R15") (pin "2") (pinfunction "2_2") (pintype "passive"))
      (node (ref "TP1") (pin "1") (pinfunction "12_1") (pintype "passive"))
      (node (ref "U2") (pin "25") (pinfunction "XTI/MCLK_25") (pintype "passive"))
    )
    (net (code "37") (name "Net-(U1-ADCDAT)") (class "Default")
      (node (ref "R11") (pin "6") (pinfunction "6_6") (pintype "passive"))
      (node (ref "U1") (pin "6") (pinfunction "ADCDAT_6") (pintype "passive"))
    )
    (net (code "38") (name "Net-(U1-ADC_LRC)") (class "Default")
      (node (ref "R11") (pin "5") (pinfunction "5_5") (pintype "passive"))
      (node (ref "U1") (pin "5") (pinfunction "DACLRC_5") (pintype "passive"))
      (node (ref "U1") (pin "7") (pinfunction "ADC_LRC_7") (pintype "passive"))
    )
    (net (code "39") (name "Net-(U1-BCLK)") (class "Default")
      (node (ref "R11") (pin "8") (pinfunction "8_8") (pintype "passive"))
      (node (ref "U1") (pin "3") (pinfunction "BCLK_3") (pintype "passive"))
    )
    (net (code "40") (name "Net-(U1-CLKOUT)") (class "Default")
      (node (ref "R15") (pin "1") (pinfunction "1_1") (pintype "passive"))
      (node (ref "U1") (pin "2") (pinfunction "CLKOUT_2") (pintype "passive"))
    )
    (net (code "41") (name "Net-(U1-DACDAT)") (class "Default")
      (node (ref "R11") (pin "7") (pinfunction "7_7") (pintype "passive"))
      (node (ref "U1") (pin "4") (pinfunction "DACDAT_4") (pintype "passive"))
    )
    (net (code "42") (name "Net-(U1-LHPOUT)") (class "Default")
      (node (ref "C21") (pin "1") (pinfunction "1_1") (pintype "passive"))
      (node (ref "U1") (pin "9") (pinfunction "LHPOUT_9") (pintype "passive"))
    )
    (net (code "43") (name "Net-(U1-LLINEIN)") (class "Default")
      (node (ref "C11") (pin "1") (pinfunction "1_1") (pintype "passive"))
      (node (ref "U1") (pin "20") (pinfunction "LLINEIN_20") (pintype "passive"))
    )
    (net (code "44") (name "Net-(U1-RHPOUT)") (class "Default")
      (node (ref "C23") (pin "1") (pinfunction "1_1") (pintype "passive"))
      (node (ref "U1") (pin "10") (pinfunction "RHPOUT_10") (pintype "passive"))
    )
    (net (code "45") (name "Net-(U1-RLINEIN)") (class "Default")
      (node (ref "C17") (pin "1") (pinfunction "1_1") (pintype "passive"))
      (node (ref "U1") (pin "19") (pinfunction "RLINEIN_19") (pintype "passive"))
    )
    (net (code "46") (name "Net-(U1-VMID)") (class "Default")
      (node (ref "C25") (pin "1") (pinfunction "1_1") (pintype "passive"))
      (node (ref "C26") (pin "1") (pinfunction "1_1") (pintype "passive"))
      (node (ref "U1") (pin "16") (pinfunction "VMID_16") (pintype "passive"))
    )
    (net (code "47") (name "Net-(U1-XTI{slash}MCLK)") (class "Default")
      (node (ref "C30") (pin "1") (pinfunction "1_1") (pintype "passive"))
      (node (ref "R17") (pin "1") (pinfunction "1_1") (pintype "passive"))
      (node (ref "U1") (pin "25") (pinfunction "XTI/MCLK_25") (pintype "passive"))
      (node (ref "Y1") (pin "1") (pinfunction "1_1") (pintype "passive"))
    )
    (net (code "48") (name "Net-(U1-XTO)") (class "Default")
      (node (ref "C31") (pin "1") (pinfunction "1_1") (pintype "passive"))
      (node (ref "R17") (pin "2") (pinfunction "2_2") (pintype "passive"))
      (node (ref "U1") (pin "26") (pinfunction "XTO_26") (pintype "passive"))
      (node (ref "Y1") (pin "3") (pinfunction "3_3") (pintype "passive"))
    )
    (net (code "49") (name "Net-(U2-ADCDAT)") (class "Default")
      (node (ref "R12") (pin "7") (pinfunction "7_7") (pintype "passive"))
      (node (ref "U2") (pin "6") (pinfunction "ADCDAT_6") (pintype "passive"))
    )
    (net (code "50") (name "Net-(U2-ADC_LRC)") (class "Default")
      (node (ref "R12") (pin "8") (pinfunction "8_8") (pintype "passive"))
      (node (ref "U2") (pin "5") (pinfunction "DACLRC_5") (pintype "passive"))
      (node (ref "U2") (pin "7") (pinfunction "ADC_LRC_7") (pintype "passive"))
    )
    (net (code "51") (name "Net-(U2-BCLK)") (class "Default")
      (node (ref "R12") (pin "5") (pinfunction "5_5") (pintype "passive"))
      (node (ref "U2") (pin "3") (pinfunction "BCLK_3") (pintype "passive"))
    )
    (net (code "52") (name "Net-(U2-CLKOUT)") (class "Default")
      (node (ref "R16") (pin "1") (pinfunction "1_1") (pintype "passive"))
      (node (ref "U2") (pin "2") (pinfunction "CLKOUT_2") (pintype "passive"))
    )
    (net (code "53") (name "Net-(U2-DACDAT)") (class "Default")
      (node (ref "R12") (pin "6") (pinfunction "6_6") (pintype "passive"))
      (node (ref "U2") (pin "4") (pinfunction "DACDAT_4") (pintype "passive"))
    )
    (net (code "54") (name "Net-(U2-LHPOUT)") (class "Default")
      (node (ref "C22") (pin "1") (pinfunction "1_1") (pintype "passive"))
      (node (ref "U2") (pin "9") (pinfunction "LHPOUT_9") (pintype "passive"))
    )
    (net (code "55") (name "Net-(U2-LLINEIN)") (class "Default")
      (node (ref "C12") (pin "1") (pinfunction "1_1") (pintype "passive"))
      (node (ref "U2") (pin "20") (pinfunction "LLINEIN_20") (pintype "passive"))
    )
    (net (code "56") (name "Net-(U2-RHPOUT)") (class "Default")
      (node (ref "C24") (pin "1") (pinfunction "1_1") (pintype "passive"))
      (node (ref "U2") (pin "10") (pinfunction "RHPOUT_10") (pintype "passive"))
    )
    (net (code "57") (name "Net-(U2-RLINEIN)") (class "Default")
      (node (ref "C18") (pin "1") (pinfunction "1_1") (pintype "passive"))
      (node (ref "U2") (pin "19") (pinfunction "RLINEIN_19") (pintype "passive"))
    )
    (net (code "58") (name "Net-(U2-VMID)") (class "Default")
      (node (ref "C27") (pin "1") (pinfunction "1_1") (pintype "passive"))
      (node (ref "C28") (pin "1") (pinfunction "1_1") (pintype "passive"))
      (node (ref "U2") (pin "16") (pinfunction "VMID_16") (pintype "passive"))
    )
    (net (code "59") (name "Net-(U2-XTO)") (class "Default")
      (node (ref "C29") (pin "1") (pinfunction "1_1") (pintype "passive"))
      (node (ref "U2") (pin "26") (pinfunction "XTO_26") (pintype "passive"))
    )
    (net (code "60") (name "unconnected-(H1-Pad2)") (class "Default")
      (node (ref "H1") (pin "2") (pinfunction "2_2") (pintype "passive"))
    )
    (net (code "61") (name "unconnected-(H1-Pad3)") (class "Default")
      (node (ref "H1") (pin "3") (pinfunction "3_3") (pintype "passive"))
    )
    (net (code "62") (name "unconnected-(H1-Pad4)") (class "Default")
      (node (ref "H1") (pin "4") (pinfunction "4_4") (pintype "passive"))
    )
    (net (code "63") (name "unconnected-(H1-Pad5)") (class "Default")
      (node (ref "H1") (pin "5") (pinfunction "5_5") (pintype "passive"))
    )
    (net (code "64") (name "unconnected-(H1-Pad6)") (class "Default")
      (node (ref "H1") (pin "6") (pinfunction "6_6") (pintype "passive"))
    )
    (net (code "65") (name "unconnected-(H1-Pad7)") (class "Default")
      (node (ref "H1") (pin "7") (pinfunction "7_7") (pintype "passive"))
    )
    (net (code "66") (name "unconnected-(H1-Pad8)") (class "Default")
      (node (ref "H1") (pin "8") (pinfunction "8_8") (pintype "passive"))
    )
    (net (code "67") (name "unconnected-(H1-Pad9)") (class "Default")
      (node (ref "H1") (pin "9") (pinfunction "9_9") (pintype "passive"))
    )
    (net (code "68") (name "unconnected-(H1-Pad10)") (class "Default")
      (node (ref "H1") (pin "10") (pinfunction "10_10") (pintype "passive"))
    )
    (net (code "69") (name "unconnected-(H1-Pad11)") (class "Default")
      (node (ref "H1") (pin "11") (pinfunction "11_11") (pintype "passive"))
    )
    (net (code "70") (name "unconnected-(H1-Pad12)") (class "Default")
      (node (ref "H1") (pin "12") (pinfunction "12_12") (pintype "passive"))
    )
    (net (code "71") (name "unconnected-(H1-Pad13)") (class "Default")
      (node (ref "H1") (pin "13") (pinfunction "13_13") (pintype "passive"))
    )
    (net (code "72") (name "unconnected-(H1-Pad14)") (class "Default")
      (node (ref "H1") (pin "14") (pinfunction "14_14") (pintype "passive"))
    )
    (net (code "73") (name "unconnected-(H1-Pad18)") (class "Default")
      (node (ref "H1") (pin "18") (pinfunction "18_18") (pintype "passive"))
    )
    (net (code "74") (name "unconnected-(H1-Pad19)") (class "Default")
      (node (ref "H1") (pin "19") (pinfunction "19_19") (pintype "passive"))
    )
    (net (code "75") (name "unconnected-(H1-Pad20)") (class "Default")
      (node (ref "H1") (pin "20") (pinfunction "20_20") (pintype "passive"))
    )
    (net (code "76") (name "unconnected-(H1-Pad21)") (class "Default")
      (node (ref "H1") (pin "21") (pinfunction "21_21") (pintype "passive"))
    )
    (net (code "77") (name "unconnected-(H1-Pad22)") (class "Default")
      (node (ref "H1") (pin "22") (pinfunction "22_22") (pintype "passive"))
    )
    (net (code "78") (name "unconnected-(H1-Pad27)") (class "Default")
      (node (ref "H1") (pin "27") (pinfunction "27_27") (pintype "passive"))
    )
    (net (code "79") (name "unconnected-(H1-Pad29)") (class "Default")
      (node (ref "H1") (pin "29") (pinfunction "29_29") (pintype "passive"))
    )
    (net (code "80") (name "unconnected-(H1-Pad30)") (class "Default")
      (node (ref "H1") (pin "30") (pinfunction "30_30") (pintype "passive"))
    )
    (net (code "81") (name "unconnected-(H1-Pad31)") (class "Default")
      (node (ref "H1") (pin "31") (pinfunction "31_31") (pintype "passive"))
    )
    (net (code "82") (name "unconnected-(H1-Pad32)") (class "Default")
      (node (ref "H1") (pin "32") (pinfunction "32_32") (pintype "passive"))
    )
    (net (code "83") (name "unconnected-(H1-Pad34)") (class "Default")
      (node (ref "H1") (pin "34") (pinfunction "34_34") (pintype "passive"))
    )
    (net (code "84") (name "unconnected-(H1-Pad35)") (class "Default")
      (node (ref "H1") (pin "35") (pinfunction "35_35") (pintype "passive"))
    )
    (net (code "85") (name "unconnected-(H1-Pad36)") (class "Default")
      (node (ref "H1") (pin "36") (pinfunction "36_36") (pintype "passive"))
    )
    (net (code "86") (name "unconnected-(H1-Pad37)") (class "Default")
      (node (ref "H1") (pin "37") (pinfunction "37_37") (pintype "passive"))
    )
    (net (code "87") (name "unconnected-(H1-Pad38)") (class "Default")
      (node (ref "H1") (pin "38") (pinfunction "38_38") (pintype "passive"))
    )
    (net (code "88") (name "unconnected-(H1-Pad39)") (class "Default")
      (node (ref "H1") (pin "39") (pinfunction "39_39") (pintype "passive"))
    )
    (net (code "89") (name "unconnected-(H1-Pad40)") (class "Default")
      (node (ref "H1") (pin "40") (pinfunction "40_40") (pintype "passive"))
    )
    (net (code "90") (name "unconnected-(H1-Pad41)") (class "Default")
      (node (ref "H1") (pin "41") (pinfunction "41_41") (pintype "passive"))
    )
    (net (code "91") (name "unconnected-(H1-Pad42)") (class "Default")
      (node (ref "H1") (pin "42") (pinfunction "42_42") (pintype "passive"))
    )
    (net (code "92") (name "unconnected-(H1-Pad43)") (class "Default")
      (node (ref "H1") (pin "43") (pinfunction "43_43") (pintype "passive"))
    )
    (net (code "93") (name "unconnected-(H1-Pad44)") (class "Default")
      (node (ref "H1") (pin "44") (pinfunction "44_44") (pintype "passive"))
    )
    (net (code "94") (name "unconnected-(H1-Pad45)") (class "Default")
      (node (ref "H1") (pin "45") (pinfunction "45_45") (pintype "passive"))
    )
    (net (code "95") (name "unconnected-(H1-Pad46)") (class "Default")
      (node (ref "H1") (pin "46") (pinfunction "46_46") (pintype "passive"))
    )
    (net (code "96") (name "unconnected-(H1-Pad47)") (class "Default")
      (node (ref "H1") (pin "47") (pinfunction "47_47") (pintype "passive"))
    )
    (net (code "97") (name "unconnected-(H2-Pad2)") (class "Default")
      (node (ref "H2") (pin "2") (pinfunction "2_2") (pintype "passive"))
    )
    (net (code "98") (name "unconnected-(H2-Pad3)") (class "Default")
      (node (ref "H2") (pin "3") (pinfunction "3_3") (pintype "passive"))
    )
    (net (code "99") (name "unconnected-(H2-Pad4)") (class "Default")
      (node (ref "H2") (pin "4") (pinfunction "4_4") (pintype "passive"))
    )
    (net (code "100") (name "unconnected-(H2-Pad5)") (class "Default")
      (node (ref "H2") (pin "5") (pinfunction "5_5") (pintype "passive"))
    )
    (net (code "101") (name "unconnected-(H2-Pad6)") (class "Default")
      (node (ref "H2") (pin "6") (pinfunction "6_6") (pintype "passive"))
    )
    (net (code "102") (name "unconnected-(H2-Pad7)") (class "Default")
      (node (ref "H2") (pin "7") (pinfunction "7_7") (pintype "passive"))
    )
    (net (code "103") (name "unconnected-(H2-Pad8)") (class "Default")
      (node (ref "H2") (pin "8") (pinfunction "8_8") (pintype "passive"))
    )
    (net (code "104") (name "unconnected-(H2-Pad9)") (class "Default")
      (node (ref "H2") (pin "9") (pinfunction "9_9") (pintype "passive"))
    )
    (net (code "105") (name "unconnected-(H2-Pad10)") (class "Default")
      (node (ref "H2") (pin "10") (pinfunction "10_10") (pintype "passive"))
    )
    (net (code "106") (name "unconnected-(H2-Pad11)") (class "Default")
      (node (ref "H2") (pin "11") (pinfunction "11_11") (pintype "passive"))
    )
    (net (code "107") (name "unconnected-(H2-Pad12)") (class "Default")
      (node (ref "H2") (pin "12") (pinfunction "12_12") (pintype "passive"))
    )
    (net (code "108") (name "unconnected-(H2-Pad13)") (class "Default")
      (node (ref "H2") (pin "13") (pinfunction "13_13") (pintype "passive"))
    )
    (net (code "109") (name "unconnected-(H2-Pad14)") (class "Default")
      (node (ref "H2") (pin "14") (pinfunction "14_14") (pintype "passive"))
    )
    (net (code "110") (name "unconnected-(H2-Pad15)") (class "Default")
      (node (ref "H2") (pin "15") (pinfunction "15_15") (pintype "passive"))
    )
    (net (code "111") (name "unconnected-(H2-Pad16)") (class "Default")
      (node (ref "H2") (pin "16") (pinfunction "16_16") (pintype "passive"))
    )
    (net (code "112") (name "unconnected-(H2-Pad17)") (class "Default")
      (node (ref "H2") (pin "17") (pinfunction "17_17") (pintype "passive"))
    )
    (net (code "113") (name "unconnected-(H2-Pad18)") (class "Default")
      (node (ref "H2") (pin "18") (pinfunction "18_18") (pintype "passive"))
    )
    (net (code "114") (name "unconnected-(H2-Pad19)") (class "Default")
      (node (ref "H2") (pin "19") (pinfunction "19_19") (pintype "passive"))
    )
    (net (code "115") (name "unconnected-(H2-Pad20)") (class "Default")
      (node (ref "H2") (pin "20") (pinfunction "20_20") (pintype "passive"))
    )
    (net (code "116") (name "unconnected-(H2-Pad21)") (class "Default")
      (node (ref "H2") (pin "21") (pinfunction "21_21") (pintype "passive"))
    )
    (net (code "117") (name "unconnected-(H2-Pad22)") (class "Default")
      (node (ref "H2") (pin "22") (pinfunction "22_22") (pintype "passive"))
    )
    (net (code "118") (name "unconnected-(H2-Pad23)") (class "Default")
      (node (ref "H2") (pin "23") (pinfunction "23_23") (pintype "passive"))
    )
    (net (code "119") (name "unconnected-(H2-Pad24)") (class "Default")
      (node (ref "H2") (pin "24") (pinfunction "24_24") (pintype "passive"))
    )
    (net (code "120") (name "unconnected-(H2-Pad25)") (class "Default")
      (node (ref "H2") (pin "25") (pinfunction "25_25") (pintype "passive"))
    )
    (net (code "121") (name "unconnected-(H2-Pad29)") (class "Default")
      (node (ref "H2") (pin "29") (pinfunction "29_29") (pintype "passive"))
    )
    (net (code "122") (name "unconnected-(H2-Pad30)") (class "Default")
      (node (ref "H2") (pin "30") (pinfunction "30_30") (pintype "passive"))
    )
    (net (code "123") (name "unconnected-(H2-Pad31)") (class "Default")
      (node (ref "H2") (pin "31") (pinfunction "31_31") (pintype "passive"))
    )
    (net (code "124") (name "unconnected-(H2-Pad32)") (class "Default")
      (node (ref "H2") (pin "32") (pinfunction "32_32") (pintype "passive"))
    )
    (net (code "125") (name "unconnected-(H2-Pad33)") (class "Default")
      (node (ref "H2") (pin "33") (pinfunction "33_33") (pintype "passive"))
    )
    (net (code "126") (name "unconnected-(H2-Pad34)") (class "Default")
      (node (ref "H2") (pin "34") (pinfunction "34_34") (pintype "passive"))
    )
    (net (code "127") (name "unconnected-(H2-Pad35)") (class "Default")
      (node (ref "H2") (pin "35") (pinfunction "35_35") (pintype "passive"))
    )
    (net (code "128") (name "unconnected-(H2-Pad38)") (class "Default")
      (node (ref "H2") (pin "38") (pinfunction "38_38") (pintype "passive"))
    )
    (net (code "129") (name "unconnected-(H2-Pad39)") (class "Default")
      (node (ref "H2") (pin "39") (pinfunction "39_39") (pintype "passive"))
    )
    (net (code "130") (name "unconnected-(H2-Pad40)") (class "Default")
      (node (ref "H2") (pin "40") (pinfunction "40_40") (pintype "passive"))
    )
    (net (code "131") (name "unconnected-(H2-Pad41)") (class "Default")
      (node (ref "H2") (pin "41") (pinfunction "41_41") (pintype "passive"))
    )
    (net (code "132") (name "unconnected-(H2-Pad42)") (class "Default")
      (node (ref "H2") (pin "42") (pinfunction "42_42") (pintype "passive"))
    )
    (net (code "133") (name "unconnected-(H2-Pad43)") (class "Default")
      (node (ref "H2") (pin "43") (pinfunction "43_43") (pintype "passive"))
    )
    (net (code "134") (name "unconnected-(H2-Pad44)") (class "Default")
      (node (ref "H2") (pin "44") (pinfunction "44_44") (pintype "passive"))
    )
    (net (code "135") (name "unconnected-(H2-Pad45)") (class "Default")
      (node (ref "H2") (pin "45") (pinfunction "45_45") (pintype "passive"))
    )
    (net (code "136") (name "unconnected-(H2-Pad46)") (class "Default")
      (node (ref "H2") (pin "46") (pinfunction "46_46") (pintype "passive"))
    )
    (net (code "137") (name "unconnected-(H2-Pad47)") (class "Default")
      (node (ref "H2") (pin "47") (pinfunction "47_47") (pintype "passive"))
    )
    (net (code "138") (name "unconnected-(J1-4-Pad6)") (class "Default")
      (node (ref "J1") (pin "6") (pinfunction "4_6") (pintype "passive"))
    )
    (net (code "139") (name "unconnected-(J2-4-Pad6)") (class "Default")
      (node (ref "J2") (pin "6") (pinfunction "4_6") (pintype "passive"))
    )
    (net (code "140") (name "unconnected-(J3-3-Pad5)") (class "Default")
      (node (ref "J3") (pin "5") (pinfunction "3_5") (pintype "passive"))
    )
    (net (code "141") (name "unconnected-(J3-4-Pad6)") (class "Default")
      (node (ref "J3") (pin "6") (pinfunction "4_6") (pintype "passive"))
    )
    (net (code "142") (name "unconnected-(J4-3-Pad5)") (class "Default")
      (node (ref "J4") (pin "5") (pinfunction "3_5") (pintype "passive"))
    )
    (net (code "143") (name "unconnected-(J4-4-Pad6)") (class "Default")
      (node (ref "J4") (pin "6") (pinfunction "4_6") (pintype "passive"))
    )
    (net (code "144") (name "unconnected-(J5-3-Pad5)") (class "Default")
      (node (ref "J5") (pin "5") (pinfunction "3_5") (pintype "passive"))
    )
    (net (code "145") (name "unconnected-(J5-4-Pad6)") (class "Default")
      (node (ref "J5") (pin "6") (pinfunction "4_6") (pintype "passive"))
    )
    (net (code "146") (name "unconnected-(J6-3-Pad5)") (class "Default")
      (node (ref "J6") (pin "5") (pinfunction "3_5") (pintype "passive"))
    )
    (net (code "147") (name "unconnected-(J6-4-Pad6)") (class "Default")
      (node (ref "J6") (pin "6") (pinfunction "4_6") (pintype "passive"))
    )
    (net (code "148") (name "unconnected-(J7-3-Pad5)") (class "Default")
      (node (ref "J7") (pin "5") (pinfunction "3_5") (pintype "passive"))
    )
    (net (code "149") (name "unconnected-(J7-4-Pad6)") (class "Default")
      (node (ref "J7") (pin "6") (pinfunction "4_6") (pintype "passive"))
    )
    (net (code "150") (name "unconnected-(J8-3-Pad5)") (class "Default")
      (node (ref "J8") (pin "5") (pinfunction "3_5") (pintype "passive"))
    )
    (net (code "151") (name "unconnected-(J8-4-Pad6)") (class "Default")
      (node (ref "J8") (pin "6") (pinfunction "4_6") (pintype "passive"))
    )
    (net (code "152") (name "unconnected-(J9-3-Pad5)") (class "Default")
      (node (ref "J9") (pin "5") (pinfunction "3_5") (pintype "passive"))
    )
    (net (code "153") (name "unconnected-(J9-4-Pad6)") (class "Default")
      (node (ref "J9") (pin "6") (pinfunction "4_6") (pintype "passive"))
    )
    (net (code "154") (name "unconnected-(J10-3-Pad5)") (class "Default")
      (node (ref "J10") (pin "5") (pinfunction "3_5") (pintype "passive"))
    )
    (net (code "155") (name "unconnected-(J10-4-Pad6)") (class "Default")
      (node (ref "J10") (pin "6") (pinfunction "4_6") (pintype "passive"))
    )
    (net (code "156") (name "unconnected-(U1-MICBIAS-Pad17)") (class "Default")
      (node (ref "U1") (pin "17") (pinfunction "MICBIAS_17") (pintype "passive"))
    )
    (net (code "157") (name "unconnected-(U1-MICIN-Pad18)") (class "Default")
      (node (ref "U1") (pin "18") (pinfunction "MICIN_18") (pintype "passive"))
    )
    (net (code "158") (name "unconnected-(U2-MICBIAS-Pad17)") (class "Default")
      (node (ref "U2") (pin "17") (pinfunction "MICBIAS_17") (pintype "passive"))
    )
    (net (code "159") (name "unconnected-(U2-MICIN-Pad18)") (class "Default")
      (node (ref "U2") (pin "18") (pinfunction "MICIN_18") (pintype "passive"))
    )
  )
)
